# PowerSupply.net
KiCad netlist of a schematic drawn in Altium Designer
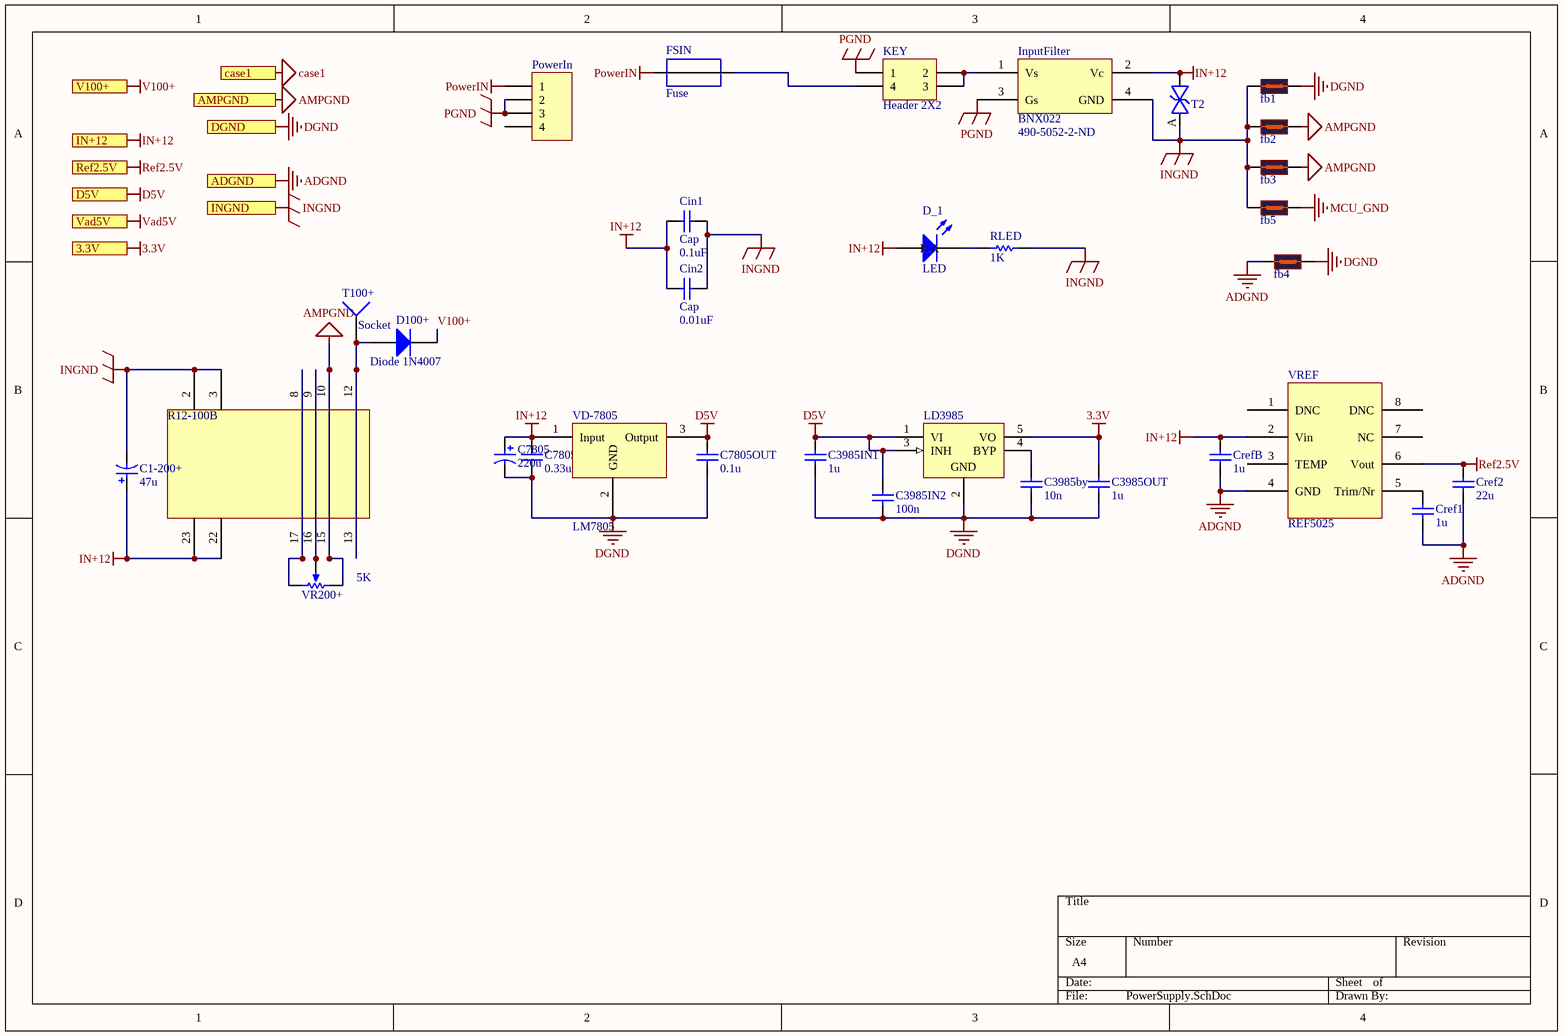
[diagram p0: PowerSupply.SchDoc]

(export (version "E")
  (design (tool "Eeschema 10.0.6"))
  (components
    (comp (ref "C1-200+")
      (value "47u")
      (footprint "Cap_Rad2.5")
      (description "Capacitor (Semiconductor SIM Model)")
      (fields (field (name "PARTNO") "?"))
      (libsource (lib "Lib_AMNL") (part "Cpol"))
    )
    (comp (ref "C3985by")
      (value "10n")
      (footprint "0805")
      (description "Capacitor")
      (fields (field (name "PUBLISHER") "Altium Limited"))
      (libsource (lib "Miscellaneous Devices") (part "Cap"))
    )
    (comp (ref "C3985IN1")
      (value "1u")
      (footprint "0805")
      (description "Capacitor")
      (fields (field (name "PUBLISHER") "Altium Limited"))
      (libsource (lib "Miscellaneous Devices") (part "Cap"))
    )
    (comp (ref "C3985IN2")
      (value "100n")
      (footprint "0805")
      (description "Capacitor")
      (fields (field (name "PUBLISHER") "Altium Limited"))
      (libsource (lib "Miscellaneous Devices") (part "Cap"))
    )
    (comp (ref "C3985OUT")
      (value "1u")
      (footprint "0805")
      (description "Capacitor")
      (fields (field (name "PUBLISHER") "Altium Limited"))
      (libsource (lib "Miscellaneous Devices") (part "Cap"))
    )
    (comp (ref "C7805")
      (value "220u")
      (footprint "Cap_Rad4mm")
      (description "Capacitor (Semiconductor SIM Model)")
      (fields (field (name "PARTNO") "?"))
      (libsource (lib "Lib_AMNL2") (part "Cpol"))
    )
    (comp (ref "C7805IN")
      (value "0.33u")
      (footprint "0805")
      (description "Capacitor")
      (fields (field (name "PUBLISHER") "Altium Limited"))
      (libsource (lib "Miscellaneous Devices") (part "Cap"))
    )
    (comp (ref "C7805OUT")
      (value "0.1u")
      (footprint "0805")
      (description "Capacitor")
      (fields (field (name "PUBLISHER") "Altium Limited"))
      (libsource (lib "Miscellaneous Devices") (part "Cap"))
    )
    (comp (ref "Cin1")
      (value "Cap")
      (footprint "0805")
      (description "Capacitor")
      (fields (field (name "ALTIUM_VALUE") "0.1uF") (field (name "PUBLISHER") "Altium Limited"))
      (libsource (lib "Miscellaneous Devices") (part "Cap"))
    )
    (comp (ref "Cin2")
      (value "Cap")
      (footprint "0805")
      (description "Capacitor")
      (fields (field (name "ALTIUM_VALUE") "0.01uF") (field (name "PUBLISHER") "Altium Limited"))
      (libsource (lib "Miscellaneous Devices") (part "Cap"))
    )
    (comp (ref "Cref1")
      (value "1u")
      (footprint "0805")
      (description "Capacitor")
      (fields (field (name "PUBLISHER") "Altium Limited"))
      (libsource (lib "Miscellaneous Devices") (part "Cap"))
    )
    (comp (ref "Cref2")
      (value "22u")
      (footprint "0805")
      (description "Capacitor")
      (fields (field (name "PUBLISHER") "Altium Limited"))
      (libsource (lib "Miscellaneous Devices") (part "Cap"))
    )
    (comp (ref "CrefB")
      (value "1u")
      (footprint "0805")
      (description "Capacitor")
      (fields (field (name "PUBLISHER") "Altium Limited"))
      (libsource (lib "Miscellaneous Devices") (part "Cap"))
    )
    (comp (ref "D100+")
      (value "Diode 1N4007")
      (footprint "SMB")
      (description "1 Amp General Purpose Rectifier")
      (fields (field (name "PUBLISHER") "Altium Limited"))
      (libsource (lib "Miscellaneous Devices") (part "Diode 1N4007"))
    )
    (comp (ref "D_1")
      (value "LED")
      (footprint "LIGHT")
      (description "Typical INFRARED GaAs LED")
      (fields (field (name "PUBLISHER") "Altium Limited"))
      (libsource (lib "NanControlSlot") (part "LED0"))
    )
    (comp (ref "fb1")
      (value "MH2029-300YCT-ND")
      (footprint "FB_0805")
      (description "Ferrite bead")
      (libsource (lib "Lib_AMNL") (part "FerriteBead"))
    )
    (comp (ref "fb2")
      (value "MH2029-300YCT-ND")
      (footprint "FB_0805")
      (description "Ferrite bead")
      (libsource (lib "Lib_AMNL") (part "FerriteBead"))
    )
    (comp (ref "fb3")
      (value "MH2029-300YCT-ND")
      (footprint "FB_0805")
      (description "Ferrite bead")
      (libsource (lib "Lib_AMNL") (part "FerriteBead"))
    )
    (comp (ref "fb4")
      (value "MH2029-300YCT-ND")
      (footprint "FB_0805")
      (description "Ferrite bead")
      (libsource (lib "Lib_AMNL") (part "FerriteBead"))
    )
    (comp (ref "fb5")
      (value "MH2029-300YCT-ND")
      (footprint "FB_0805")
      (description "Ferrite bead")
      (libsource (lib "Lib_AMNL") (part "FerriteBead"))
    )
    (comp (ref "FSIN")
      (value "Fuse")
      (footprint "FuseHolder")
      (fields (field (name "PARTNO") "?"))
      (libsource (lib "Lib_AMNL") (part "Fuse"))
    )
    (comp (ref "InputFilter")
      (value "BNX022")
      (footprint "BNX022")
      (fields (field (name "SUPPLIER PART NUMBER 1") "490-5052-2-ND"))
      (libsource (lib "Lib_AMNL") (part "BNX022"))
    )
    (comp (ref "KEY")
      (value "Header 2X2")
      (footprint "Power4Pin")
      (description "Header, 2-Pin, Dual row")
      (fields (field (name "PUBLISHER") "Altium Limited"))
      (libsource (lib "Miscellaneous Connectors") (part "Header 2X2"))
    )
    (comp (ref "LD3985")
      (value "LD3985G33R")
      (footprint "TSOT23-5L_N")
      (libsource (lib "STMicroelectronics Power Management Linear Regulator") (part "LD3985G33R"))
    )
    (comp (ref "PowerIn")
      (value "Header 4")
      (footprint "AC/DC3")
      (description "Header, 4-Pin")
      (fields (field (name "PUBLISHER") "Altium Limited"))
      (libsource (lib "Miscellaneous Connectors") (part "Header 4"))
    )
    (comp (ref "R12-100B")
      (value "R12-150B")
      (footprint "R12-150B")
      (libsource (lib "NanControlSlot") (part "R12-150B"))
    )
    (comp (ref "RLED")
      (value "1K")
      (footprint "0805")
      (description "Semiconductor Resistor, SMD")
      (fields (field (name "PARTNO") "?"))
      (libsource (lib "Lib_AMNL") (part "Rsemi"))
    )
    (comp (ref "T2")
      (value "SMAJ150CA-E3/61GICT-ND")
      (footprint "DO-214AC")
      (description "TVS, Bidirectional")
      (libsource (lib "Lib_AMNL") (part "TVS_Bi"))
    )
    (comp (ref "T100+")
      (value "Socket")
      (footprint "hole")
      (fields (field (name "PUBLISHER") "Altium Limited"))
      (libsource (lib "NanControlSlot") (part "Socket"))
    )
    (comp (ref "VD-7805")
      (value "LM7805")
      (footprint "7805")
      (libsource (lib "NanControlSlot") (part "LM7805"))
    )
    (comp (ref "VR200+")
      (value "5K")
      (footprint "VR")
      (description "Potentiometer")
      (fields (field (name "Comment") "RPot") (field (name "PUBLISHER") "Altium Limited"))
      (libsource (lib "Miscellaneous Devices") (part "RPot"))
    )
    (comp (ref "VREF") (value "REF5025") (footprint "SO8") (libsource (lib "*") (part "REF5050")))
  )
  (nets
    (net (code "1") (name "3.3V") (class "Default")
      (node (ref "C3985OUT") (pin "2") (pinfunction "2_2") (pintype "passive"))
      (node (ref "LD3985") (pin "5") (pinfunction "VO_5") (pintype "power_in"))
    )
    (net (code "2") (name "ADGND") (class "Default")
      (node (ref "Cref1") (pin "1") (pinfunction "1_1") (pintype "passive"))
      (node (ref "Cref2") (pin "1") (pinfunction "1_1") (pintype "passive"))
      (node (ref "CrefB") (pin "1") (pinfunction "1_1") (pintype "passive"))
      (node (ref "VREF") (pin "4") (pinfunction "GND_4") (pintype "passive"))
      (node (ref "fb4") (pin "1") (pinfunction "1_1") (pintype "passive"))
    )
    (net (code "3") (name "AMPGND") (class "Default")
      (node (ref "R12-100B") (pin "10") (pintype "power_in"))
      (node (ref "R12-100B") (pin "15") (pintype "power_in"))
      (node (ref "VR200+") (pin "1") (pinfunction "TOP_1") (pintype "passive"))
      (node (ref "fb2") (pin "2") (pinfunction "2_2") (pintype "passive"))
      (node (ref "fb3") (pin "2") (pinfunction "2_2") (pintype "passive"))
    )
    (net (code "4") (name "D5V") (class "Default")
      (node (ref "C3985IN1") (pin "2") (pinfunction "2_2") (pintype "passive"))
      (node (ref "C3985IN2") (pin "2") (pinfunction "2_2") (pintype "passive"))
      (node (ref "C7805OUT") (pin "2") (pinfunction "2_2") (pintype "passive"))
      (node (ref "LD3985") (pin "1") (pinfunction "VI_1") (pintype "power_in"))
      (node (ref "LD3985") (pin "3") (pinfunction "INH_3") (pintype "input"))
      (node (ref "VD-7805") (pin "3") (pinfunction "Output_3") (pintype "power_in"))
    )
    (net (code "5") (name "DGND") (class "Default")
      (node (ref "C3985IN1") (pin "1") (pinfunction "1_1") (pintype "passive"))
      (node (ref "C3985IN2") (pin "1") (pinfunction "1_1") (pintype "passive"))
      (node (ref "C3985OUT") (pin "1") (pinfunction "1_1") (pintype "passive"))
      (node (ref "C3985by") (pin "1") (pinfunction "1_1") (pintype "passive"))
      (node (ref "C7805") (pin "2") (pinfunction "-_2") (pintype "passive"))
      (node (ref "C7805IN") (pin "1") (pinfunction "1_1") (pintype "passive"))
      (node (ref "C7805OUT") (pin "1") (pinfunction "1_1") (pintype "passive"))
      (node (ref "LD3985") (pin "2") (pinfunction "GND_2") (pintype "power_in"))
      (node (ref "VD-7805") (pin "2") (pinfunction "GND_2") (pintype "power_in"))
      (node (ref "fb1") (pin "2") (pinfunction "2_2") (pintype "passive"))
      (node (ref "fb4") (pin "2") (pinfunction "2_2") (pintype "passive"))
    )
    (net (code "6") (name "IN+12") (class "Default")
      (node (ref "C1-200+") (pin "1") (pinfunction "+_1") (pintype "passive"))
      (node (ref "C7805") (pin "1") (pinfunction "+_1") (pintype "passive"))
      (node (ref "C7805IN") (pin "2") (pinfunction "2_2") (pintype "passive"))
      (node (ref "Cin1") (pin "1") (pinfunction "1_1") (pintype "passive"))
      (node (ref "Cin2") (pin "1") (pinfunction "1_1") (pintype "passive"))
      (node (ref "CrefB") (pin "2") (pinfunction "2_2") (pintype "passive"))
      (node (ref "D_1") (pin "A") (pinfunction "A_A") (pintype "passive"))
      (node (ref "InputFilter") (pin "2") (pinfunction "Vc_2") (pintype "power_in"))
      (node (ref "R12-100B") (pin "22") (pintype "power_in"))
      (node (ref "R12-100B") (pin "23") (pintype "passive"))
      (node (ref "T2") (pin "K") (pinfunction "K_K") (pintype "passive"))
      (node (ref "VD-7805") (pin "1") (pinfunction "Input_1") (pintype "power_in"))
      (node (ref "VREF") (pin "2") (pinfunction "Vin_2") (pintype "passive"))
    )
    (net (code "7") (name "INGND") (class "Default")
      (node (ref "C1-200+") (pin "2") (pinfunction "-_2") (pintype "passive"))
      (node (ref "Cin1") (pin "2") (pinfunction "2_2") (pintype "passive"))
      (node (ref "Cin2") (pin "2") (pinfunction "2_2") (pintype "passive"))
      (node (ref "InputFilter") (pin "4") (pinfunction "GND_4") (pintype "power_in"))
      (node (ref "R12-100B") (pin "2") (pintype "power_in"))
      (node (ref "R12-100B") (pin "3") (pintype "power_in"))
      (node (ref "RLED") (pin "2") (pinfunction "2_2") (pintype "passive"))
      (node (ref "T2") (pin "A") (pinfunction "A_A") (pintype "passive"))
      (node (ref "fb1") (pin "1") (pinfunction "1_1") (pintype "passive"))
      (node (ref "fb2") (pin "1") (pinfunction "1_1") (pintype "passive"))
      (node (ref "fb3") (pin "1") (pinfunction "1_1") (pintype "passive"))
      (node (ref "fb5") (pin "1") (pinfunction "1_1") (pintype "passive"))
    )
    (net (code "8") (name "MCU_GND") (class "Default")
      (node (ref "fb5") (pin "2") (pinfunction "2_2") (pintype "passive"))
    )
    (net (code "9") (name "Net-(D100+-A)") (class "Default")
      (node (ref "D100+") (pin "1") (pinfunction "A_1") (pintype "passive"))
      (node (ref "R12-100B") (pin "12") (pintype "passive"))
      (node (ref "R12-100B") (pin "13") (pintype "power_in"))
      (node (ref "T100+") (pin "1") (pinfunction "1_1") (pintype "passive"))
    )
    (net (code "10") (name "Net-(D_1-PadK)") (class "Default")
      (node (ref "D_1") (pin "K") (pinfunction "K_K") (pintype "passive"))
      (node (ref "RLED") (pin "1") (pinfunction "1_1") (pintype "passive"))
    )
    (net (code "11") (name "Net-(FSIN-Pad2)") (class "Default")
      (node (ref "FSIN") (pin "2") (pinfunction "2_2") (pintype "power_in"))
      (node (ref "KEY") (pin "4") (pinfunction "4_4") (pintype "passive"))
    )
    (net (code "12") (name "Net-(InputFilter-Vs)") (class "Default")
      (node (ref "InputFilter") (pin "1") (pinfunction "Vs_1") (pintype "power_in"))
      (node (ref "KEY") (pin "2") (pinfunction "2_2") (pintype "passive"))
      (node (ref "KEY") (pin "3") (pinfunction "3_3") (pintype "passive"))
    )
    (net (code "13") (name "Net-(LD3985-BYP)") (class "Default")
      (node (ref "C3985by") (pin "2") (pinfunction "2_2") (pintype "passive"))
      (node (ref "LD3985") (pin "4") (pinfunction "BYP_4") (pintype "passive"))
    )
    (net (code "14") (name "Net-(VR200+-BOT)") (class "Default")
      (node (ref "R12-100B") (pin "17") (pintype "power_in"))
      (node (ref "R12-100B") (pin "8") (pintype "power_in"))
      (node (ref "VR200+") (pin "2") (pinfunction "BOT_2") (pintype "passive"))
    )
    (net (code "15") (name "Net-(VR200+-TAP)") (class "Default")
      (node (ref "R12-100B") (pin "16") (pintype "power_in"))
      (node (ref "R12-100B") (pin "9") (pintype "power_in"))
      (node (ref "VR200+") (pin "3") (pinfunction "TAP_3") (pintype "passive"))
    )
    (net (code "16") (name "Net-(VREF-Trim{slash}Nr)") (class "Default")
      (node (ref "Cref1") (pin "2") (pinfunction "2_2") (pintype "passive"))
      (node (ref "VREF") (pin "5") (pinfunction "Trim/Nr_5") (pintype "passive"))
    )
    (net (code "17") (name "PGND") (class "Default")
      (node (ref "InputFilter") (pin "3") (pinfunction "Gs_3") (pintype "power_in"))
      (node (ref "KEY") (pin "1") (pinfunction "1_1") (pintype "passive"))
      (node (ref "PowerIn") (pin "2") (pinfunction "2_2") (pintype "passive"))
      (node (ref "PowerIn") (pin "3") (pinfunction "3_3") (pintype "passive"))
    )
    (net (code "18") (name "PowerIN") (class "Default")
      (node (ref "FSIN") (pin "1") (pinfunction "1_1") (pintype "power_in"))
      (node (ref "PowerIn") (pin "1") (pinfunction "1_1") (pintype "passive"))
    )
    (net (code "19") (name "Ref2.5V") (class "Default")
      (node (ref "Cref2") (pin "2") (pinfunction "2_2") (pintype "passive"))
      (node (ref "VREF") (pin "6") (pinfunction "Vout_6") (pintype "passive"))
    )
    (net (code "20") (name "V100+") (class "Default")
      (node (ref "D100+") (pin "2") (pinfunction "K_2") (pintype "passive"))
    )
    (net (code "23") (name "unconnected-(PowerIn-Pad4)") (class "Default")
      (node (ref "PowerIn") (pin "4") (pinfunction "4_4") (pintype "passive"))
    )
    (net (code "24") (name "unconnected-(VREF-DNC-Pad1)") (class "Default")
      (node (ref "VREF") (pin "1") (pinfunction "DNC_1") (pintype "passive"))
    )
    (net (code "25") (name "unconnected-(VREF-DNC-Pad8)") (class "Default")
      (node (ref "VREF") (pin "8") (pinfunction "DNC_8") (pintype "passive"))
    )
    (net (code "26") (name "unconnected-(VREF-NC-Pad7)") (class "Default")
      (node (ref "VREF") (pin "7") (pinfunction "NC_7") (pintype "passive"))
    )
    (net (code "27") (name "unconnected-(VREF-TEMP-Pad3)") (class "Default")
      (node (ref "VREF") (pin "3") (pinfunction "TEMP_3") (pintype "passive"))
    )
  )
)
